# StepperDriver_v1_0_2025-04-13_12-39-48.net
KiCad netlist of a schematic drawn in EasyEDA Pro
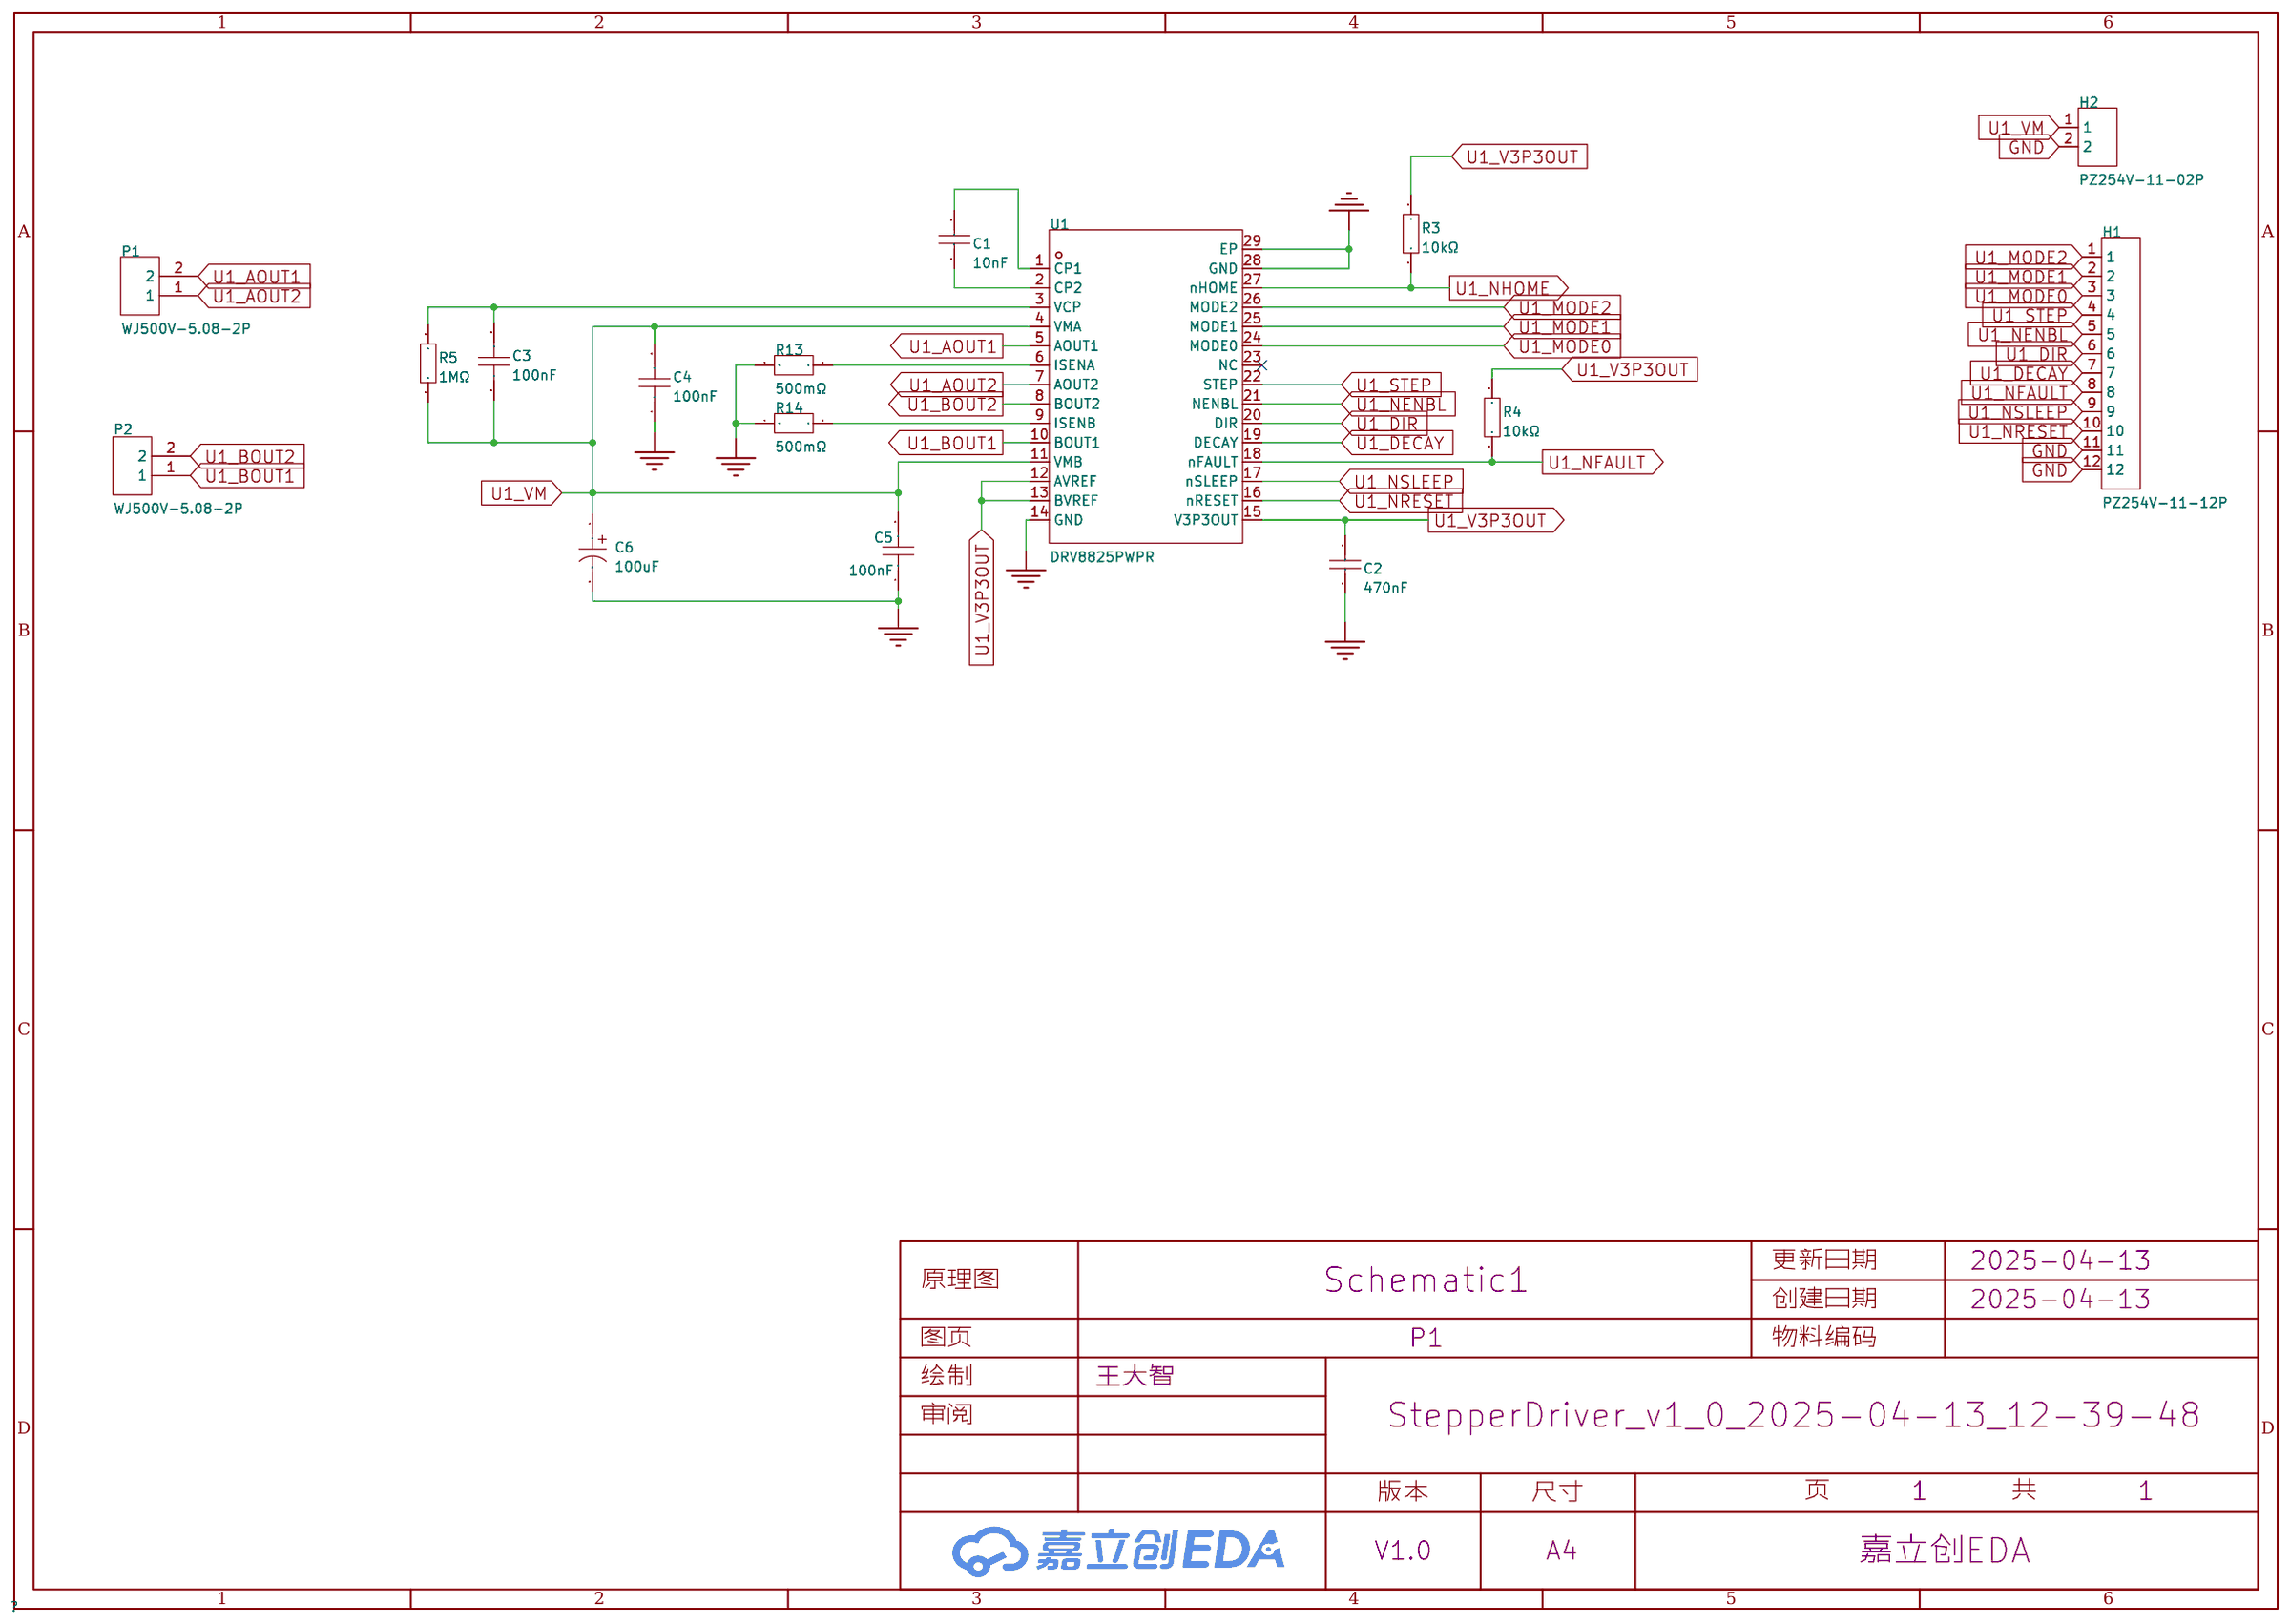
[diagram p0: schematic sheet]

(export (version "E")
  (design (tool "Eeschema 10.0.6"))
  (components
    (comp (ref "C1")
      (value "10nF")
      (footprint "easyedapro:C0603")
      (description "容值:10nF;精度:±10%;额定电压:50V;材质(温度系数):X7R;")
      (fields
        (field (name "Manufacturer Part") "CL10B103KB8NNNC")
        (field (name "Manufacturer") "SAMSUNG(三星)")
      )
      (libsource (lib "easyedapro") (part "CL10B103KB8NNNC"))
    )
    (comp (ref "C2")
      (value "470nF")
      (footprint "easyedapro:C0603")
      (description "容值:470nF;精度:±10%;额定电压:25V;材质(温度系数):X7R;")
      (fields
        (field (name "Manufacturer Part") "CL10B474KA8NNNC")
        (field (name "Manufacturer") "SAMSUNG(三星)")
      )
      (libsource (lib "easyedapro") (part "CL10B474KA8NNNC"))
    )
    (comp (ref "C3")
      (value "100nF")
      (footprint "easyedapro:C0603")
      (description "容值:100nF;精度:±10%;额定电压:50V;温度系数:X7R;")
      (fields
        (field (name "Manufacturer Part") "CGA0603X7R104K500JT")
        (field (name "Manufacturer") "HRE(芯声)")
      )
      (libsource (lib "easyedapro") (part "CGA0603X7R104K500JT"))
    )
    (comp (ref "C4")
      (value "100nF")
      (footprint "easyedapro:C0603")
      (description "容值:100nF;精度:±10%;额定电压:50V;温度系数:X7R;")
      (fields
        (field (name "Manufacturer Part") "CGA0603X7R104K500JT")
        (field (name "Manufacturer") "HRE(芯声)")
      )
      (libsource (lib "easyedapro") (part "CGA0603X7R104K500JT"))
    )
    (comp (ref "C5")
      (value "100nF")
      (footprint "easyedapro:C0603")
      (description "容值:100nF;精度:±10%;额定电压:50V;温度系数:X7R;")
      (fields
        (field (name "Manufacturer Part") "CGA0603X7R104K500JT")
        (field (name "Manufacturer") "HRE(芯声)")
      )
      (libsource (lib "easyedapro") (part "CGA0603X7R104K500JT"))
    )
    (comp (ref "C6")
      (value "100uF")
      (footprint "easyedapro:CAP-SMD_BD8.1-L8.3-W8.3-LS9.3-FD")
      (description "容值:100uF;精度:±20%;额定电压:50V;纹波电流:300mA@100kHz;等效串联电阻:600mΩ@100kHz;")
      (fields
        (field (name "Manufacturer Part") "GVE1H107M0810CNVC")
        (field (name "Manufacturer") "HRK(鸿瑞凯电子)")
      )
      (libsource (lib "easyedapro") (part "GVE1H107M0810CNVC"))
    )
    (comp (ref "H1")
      (value "PZ254V-11-12P")
      (footprint "easyedapro:HDR-TH_12P-P2.54-V-M")
      (fields (field (name "Manufacturer") "XFCN(兴飞)"))
      (libsource (lib "easyedapro") (part "PZ254V-11-12P"))
    )
    (comp (ref "H2")
      (value "PZ254V-11-02P")
      (footprint "easyedapro:HDR-TH_2P-P2.54-V-M")
      (fields (field (name "Manufacturer") "XFCN(兴飞)"))
      (libsource (lib "easyedapro") (part "PZ254V-11-02P"))
    )
    (comp (ref "P1")
      (value "WJ500V-5.08-2P")
      (footprint "easyedapro:CONN-TH_2P-P5.00_WJ500V-5.08-2P")
      (fields (field (name "Manufacturer") "KANGNEX(康奈克斯电气)"))
      (libsource (lib "easyedapro") (part "WJ500V-5.08-2P-14-00A"))
    )
    (comp (ref "P2")
      (value "WJ500V-5.08-2P")
      (footprint "easyedapro:CONN-TH_2P-P5.00_WJ500V-5.08-2P")
      (fields (field (name "Manufacturer") "KANGNEX(康奈克斯电气)"))
      (libsource (lib "easyedapro") (part "WJ500V-5.08-2P-14-00A"))
    )
    (comp (ref "R3")
      (value "10kΩ")
      (footprint "easyedapro:R0603")
      (description "电阻类型:厚膜电阻;阻值:10kΩ;精度:±1%;功率:100mW;最大工作电压:75V;温度系数:±100ppm/°C;")
      (fields (field (name "Manufacturer Part") "RC0603FR-0710KL") (field (name "Manufacturer") "YAGEO(国巨)"))
      (libsource (lib "easyedapro") (part "RC0603FR-0710KL"))
    )
    (comp (ref "R4")
      (value "10kΩ")
      (footprint "easyedapro:R0603")
      (description "电阻类型:厚膜电阻;阻值:10kΩ;精度:±1%;功率:100mW;最大工作电压:75V;温度系数:±100ppm/°C;")
      (fields (field (name "Manufacturer Part") "RC0603FR-0710KL") (field (name "Manufacturer") "YAGEO(国巨)"))
      (libsource (lib "easyedapro") (part "RC0603FR-0710KL"))
    )
    (comp (ref "R5")
      (value "1MΩ")
      (footprint "easyedapro:R0603")
      (fields
        (field (name "Manufacturer Part") "0603WAF1004T5E")
        (field (name "Manufacturer") "UNI-ROYAL(厚声)")
      )
      (libsource (lib "easyedapro") (part "电阻"))
    )
    (comp (ref "R13")
      (value "500mΩ")
      (footprint "easyedapro:R0603")
      (description "电阻类型:厚膜电阻;阻值:500mΩ;精度:±5%;功率:100mW;最大工作电压:100V;温度系数:±300ppm/°C;")
      (fields (field (name "Manufacturer Part") "FRL0603JR500TS") (field (name "Manufacturer") "FOJAN(富捷)"))
      (libsource (lib "easyedapro") (part "FRL0603JR500TS"))
    )
    (comp (ref "R14")
      (value "500mΩ")
      (footprint "easyedapro:R0603")
      (description "电阻类型:厚膜电阻;阻值:500mΩ;精度:±5%;功率:100mW;最大工作电压:100V;温度系数:±300ppm/°C;")
      (fields (field (name "Manufacturer Part") "FRL0603JR500TS") (field (name "Manufacturer") "FOJAN(富捷)"))
      (libsource (lib "easyedapro") (part "FRL0603JR500TS"))
    )
    (comp (ref "U1")
      (value "DRV8825PWPR")
      (footprint "easyedapro:HTSSOP-28_L9.7-W4.4-P0.65-LS6.4-BL-EP")
      (description "DRV8825 具有电流调节功能和 1/32 微步进的 45V、2.5A 双极步进电机驱动器")
      (fields (field (name "Manufacturer") "TI(德州仪器)"))
      (libsource (lib "easyedapro") (part "DRV8825PWPR"))
    )
  )
  (nets
    (net (code "1") (name "GND") (class "Default")
      (node (ref "C2") (pin "1") (pinfunction "1_1") (pintype "input"))
      (node (ref "C4") (pin "1") (pinfunction "1_1") (pintype "unspecified"))
      (node (ref "C5") (pin "1") (pinfunction "1_1") (pintype "unspecified"))
      (node (ref "C6") (pin "2") (pinfunction "2_2") (pintype "input"))
      (node (ref "H1") (pin "11") (pinfunction "11_11") (pintype "unspecified"))
      (node (ref "H1") (pin "12") (pinfunction "12_12") (pintype "unspecified"))
      (node (ref "H2") (pin "2") (pinfunction "2_2") (pintype "unspecified"))
      (node (ref "R13") (pin "1") (pinfunction "1_1") (pintype "unspecified"))
      (node (ref "R14") (pin "1") (pinfunction "1_1") (pintype "unspecified"))
      (node (ref "U1") (pin "14") (pinfunction "GND_14") (pintype "unspecified"))
      (node (ref "U1") (pin "28") (pinfunction "GND_28") (pintype "unspecified"))
      (node (ref "U1") (pin "29") (pinfunction "EP_29") (pintype "unspecified"))
    )
    (net (code "2") (name "Net-(U1-CP1)") (class "Default")
      (node (ref "C1") (pin "2") (pinfunction "2_2") (pintype "input"))
      (node (ref "U1") (pin "1") (pinfunction "CP1_1") (pintype "unspecified"))
    )
    (net (code "3") (name "Net-(U1-CP2)") (class "Default")
      (node (ref "C1") (pin "1") (pinfunction "1_1") (pintype "input"))
      (node (ref "U1") (pin "2") (pinfunction "CP2_2") (pintype "unspecified"))
    )
    (net (code "4") (name "Net-(U1-ISENA)") (class "Default")
      (node (ref "R13") (pin "2") (pinfunction "2_2") (pintype "unspecified"))
      (node (ref "U1") (pin "6") (pinfunction "ISENA_6") (pintype "unspecified"))
    )
    (net (code "5") (name "Net-(U1-ISENB)") (class "Default")
      (node (ref "R14") (pin "2") (pinfunction "2_2") (pintype "unspecified"))
      (node (ref "U1") (pin "9") (pinfunction "ISENB_9") (pintype "unspecified"))
    )
    (net (code "6") (name "Net-(U1-VCP)") (class "Default")
      (node (ref "C3") (pin "2") (pinfunction "2_2") (pintype "unspecified"))
      (node (ref "R5") (pin "2") (pinfunction "2_2") (pintype "input"))
      (node (ref "U1") (pin "3") (pinfunction "VCP_3") (pintype "unspecified"))
    )
    (net (code "7") (name "U1_AOUT1") (class "Default")
      (node (ref "P1") (pin "2") (pinfunction "2_2") (pintype "unspecified"))
      (node (ref "U1") (pin "5") (pinfunction "AOUT1_5") (pintype "unspecified"))
    )
    (net (code "8") (name "U1_AOUT2") (class "Default")
      (node (ref "P1") (pin "1") (pinfunction "1_1") (pintype "unspecified"))
      (node (ref "U1") (pin "7") (pinfunction "AOUT2_7") (pintype "unspecified"))
    )
    (net (code "9") (name "U1_BOUT1") (class "Default")
      (node (ref "P2") (pin "1") (pinfunction "1_1") (pintype "unspecified"))
      (node (ref "U1") (pin "10") (pinfunction "BOUT1_10") (pintype "unspecified"))
    )
    (net (code "10") (name "U1_BOUT2") (class "Default")
      (node (ref "P2") (pin "2") (pinfunction "2_2") (pintype "unspecified"))
      (node (ref "U1") (pin "8") (pinfunction "BOUT2_8") (pintype "unspecified"))
    )
    (net (code "11") (name "U1_DECAY") (class "Default")
      (node (ref "H1") (pin "7") (pinfunction "7_7") (pintype "unspecified"))
      (node (ref "U1") (pin "19") (pinfunction "DECAY_19") (pintype "unspecified"))
    )
    (net (code "12") (name "U1_DIR") (class "Default")
      (node (ref "H1") (pin "6") (pinfunction "6_6") (pintype "unspecified"))
      (node (ref "U1") (pin "20") (pinfunction "DIR_20") (pintype "unspecified"))
    )
    (net (code "13") (name "U1_MODE0") (class "Default")
      (node (ref "H1") (pin "3") (pinfunction "3_3") (pintype "unspecified"))
      (node (ref "U1") (pin "24") (pinfunction "MODE0_24") (pintype "unspecified"))
    )
    (net (code "14") (name "U1_MODE1") (class "Default")
      (node (ref "H1") (pin "2") (pinfunction "2_2") (pintype "unspecified"))
      (node (ref "U1") (pin "25") (pinfunction "MODE1_25") (pintype "unspecified"))
    )
    (net (code "15") (name "U1_MODE2") (class "Default")
      (node (ref "H1") (pin "1") (pinfunction "1_1") (pintype "unspecified"))
      (node (ref "U1") (pin "26") (pinfunction "MODE2_26") (pintype "unspecified"))
    )
    (net (code "16") (name "U1_NENBL") (class "Default")
      (node (ref "H1") (pin "5") (pinfunction "5_5") (pintype "unspecified"))
      (node (ref "U1") (pin "21") (pinfunction "NENBL_21") (pintype "unspecified"))
    )
    (net (code "17") (name "U1_NFAULT") (class "Default")
      (node (ref "H1") (pin "8") (pinfunction "8_8") (pintype "unspecified"))
      (node (ref "R4") (pin "1") (pinfunction "1_1") (pintype "input"))
      (node (ref "U1") (pin "18") (pinfunction "nFAULT_18") (pintype "unspecified"))
    )
    (net (code "18") (name "U1_NHOME") (class "Default")
      (node (ref "R3") (pin "1") (pinfunction "1_1") (pintype "input"))
      (node (ref "U1") (pin "27") (pinfunction "nHOME_27") (pintype "unspecified"))
    )
    (net (code "19") (name "U1_NRESET") (class "Default")
      (node (ref "H1") (pin "10") (pinfunction "10_10") (pintype "unspecified"))
      (node (ref "U1") (pin "16") (pinfunction "nRESET_16") (pintype "unspecified"))
    )
    (net (code "20") (name "U1_NSLEEP") (class "Default")
      (node (ref "H1") (pin "9") (pinfunction "9_9") (pintype "unspecified"))
      (node (ref "U1") (pin "17") (pinfunction "nSLEEP_17") (pintype "unspecified"))
    )
    (net (code "21") (name "U1_STEP") (class "Default")
      (node (ref "H1") (pin "4") (pinfunction "4_4") (pintype "unspecified"))
      (node (ref "U1") (pin "22") (pinfunction "STEP_22") (pintype "unspecified"))
    )
    (net (code "22") (name "U1_V3P3OUT") (class "Default")
      (node (ref "C2") (pin "2") (pinfunction "2_2") (pintype "input"))
      (node (ref "R3") (pin "2") (pinfunction "2_2") (pintype "input"))
      (node (ref "R4") (pin "2") (pinfunction "2_2") (pintype "input"))
      (node (ref "U1") (pin "12") (pinfunction "AVREF_12") (pintype "unspecified"))
      (node (ref "U1") (pin "13") (pinfunction "BVREF_13") (pintype "unspecified"))
      (node (ref "U1") (pin "15") (pinfunction "V3P3OUT_15") (pintype "unspecified"))
    )
    (net (code "23") (name "U1_VM") (class "Default")
      (node (ref "C3") (pin "1") (pinfunction "1_1") (pintype "unspecified"))
      (node (ref "C4") (pin "2") (pinfunction "2_2") (pintype "unspecified"))
      (node (ref "C5") (pin "2") (pinfunction "2_2") (pintype "unspecified"))
      (node (ref "C6") (pin "1") (pinfunction "1_1") (pintype "input"))
      (node (ref "H2") (pin "1") (pinfunction "1_1") (pintype "unspecified"))
      (node (ref "R5") (pin "1") (pinfunction "1_1") (pintype "input"))
      (node (ref "U1") (pin "11") (pinfunction "VMB_11") (pintype "unspecified"))
      (node (ref "U1") (pin "4") (pinfunction "VMA_4") (pintype "unspecified"))
    )
    (net (code "24") (name "unconnected-(U1-NC-Pad23)") (class "Default")
      (node (ref "U1") (pin "23") (pinfunction "NC_23") (pintype "unspecified+no_connect"))
    )
  )
)
